# PowerSupply.net
KiCad netlist of a schematic drawn in Altium Designer
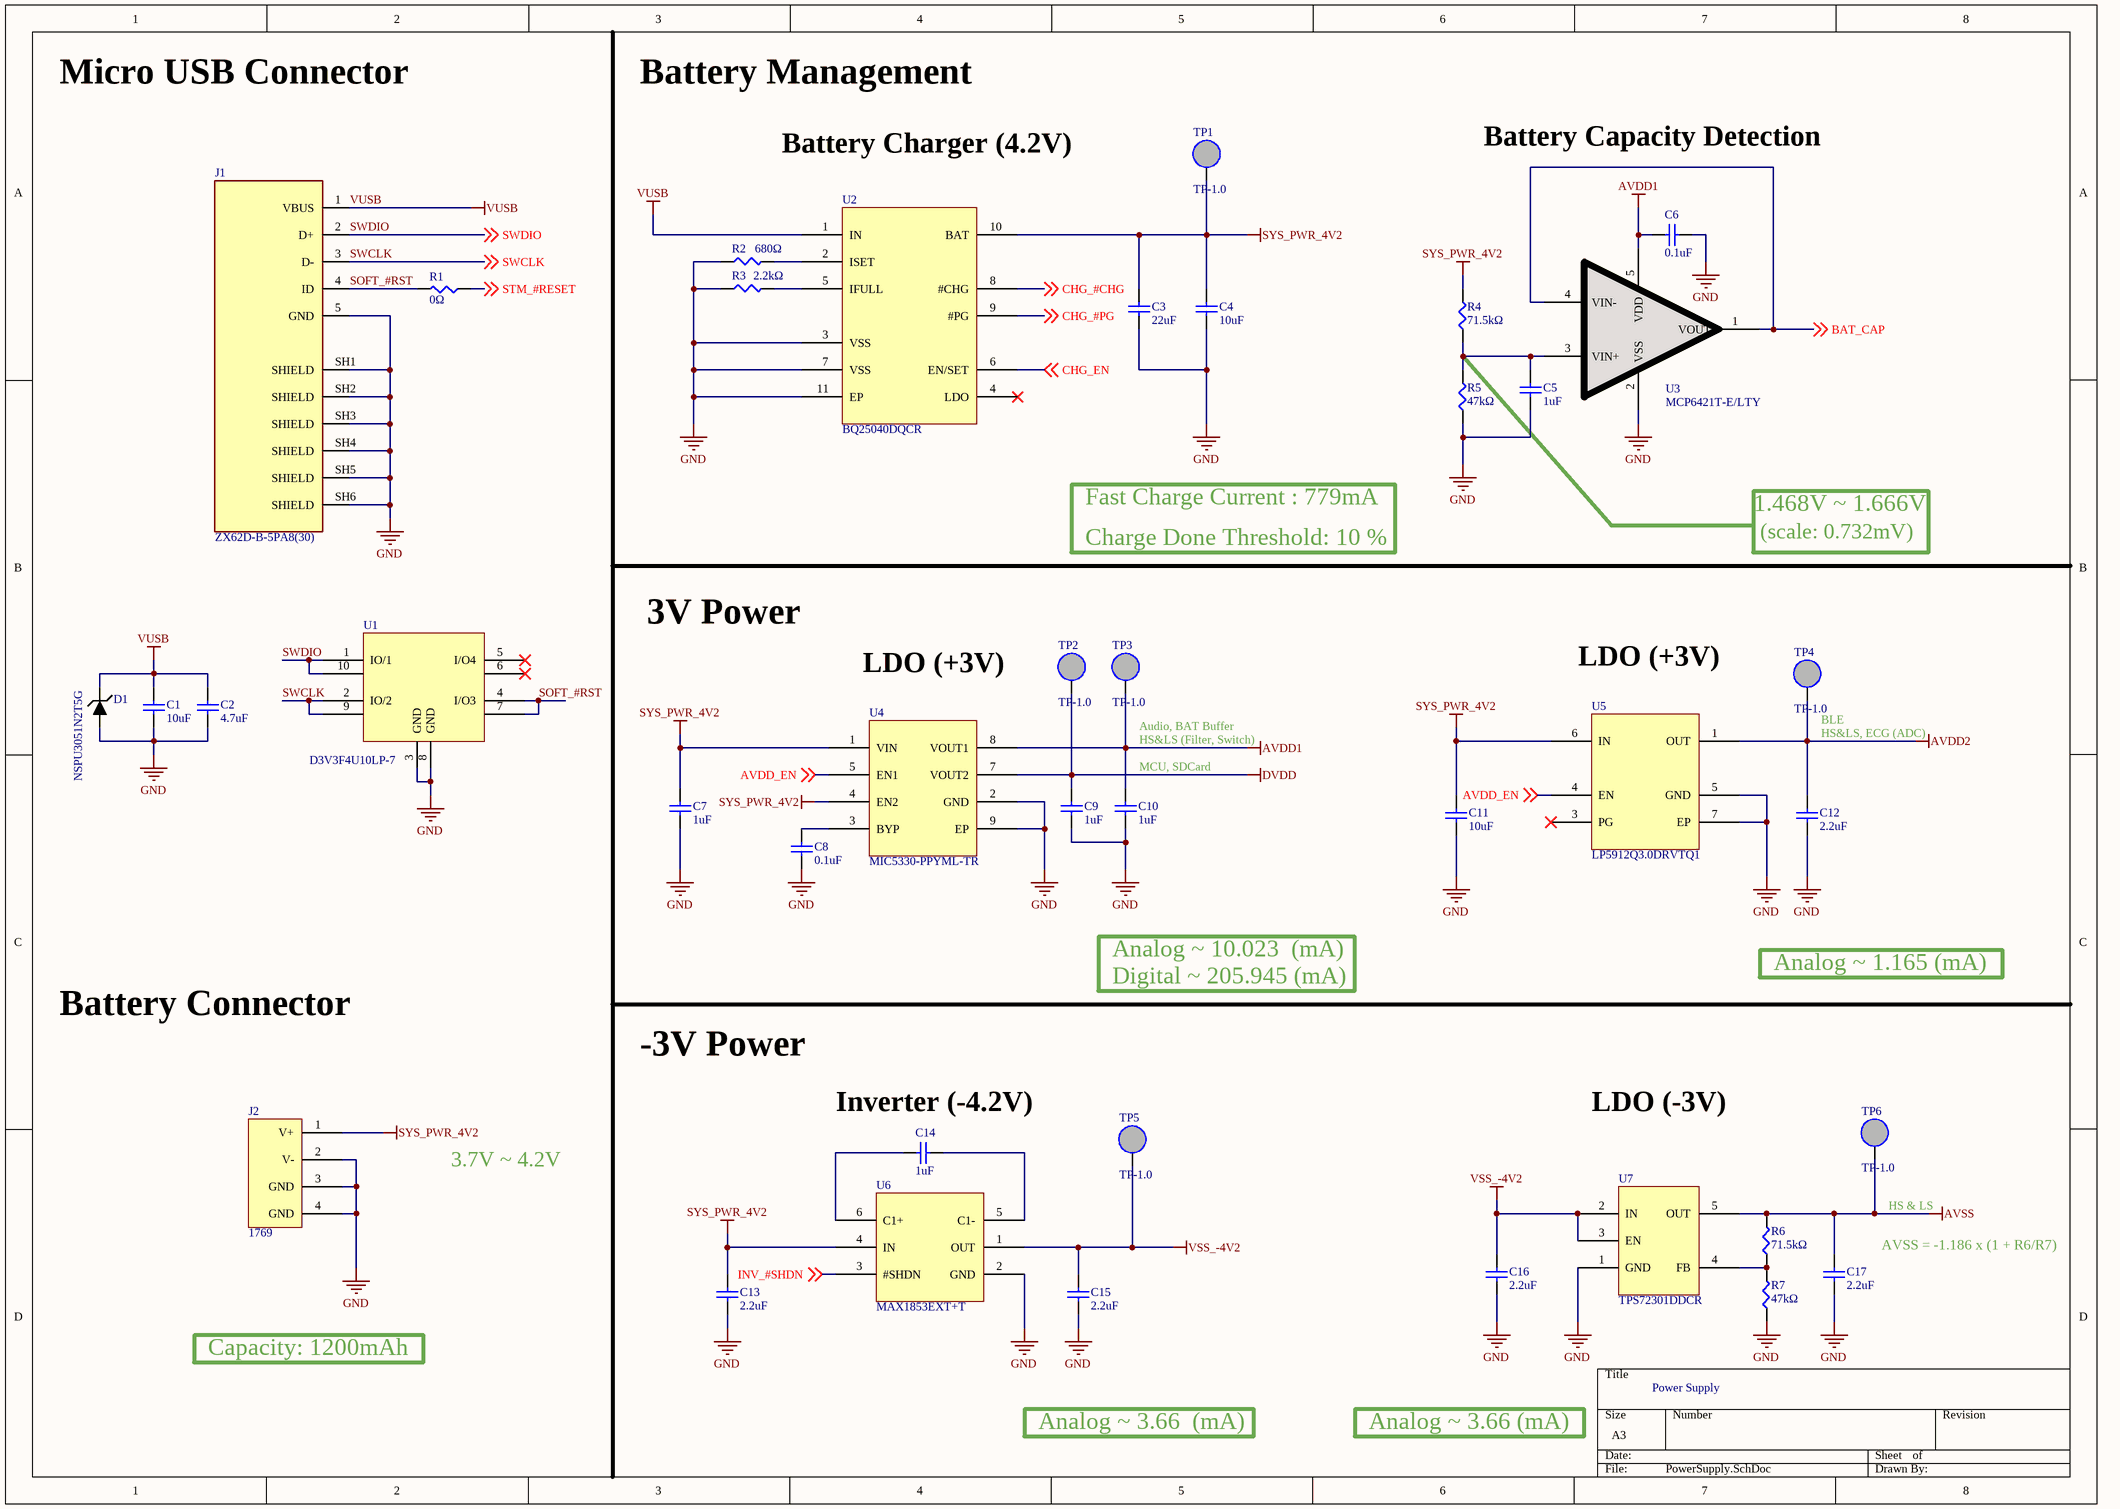
[diagram p0: PowerSupply.SchDoc]

(export (version "E")
  (design (tool "Eeschema 10.0.6"))
  (components
    (comp (ref "C1")
      (value "10uF")
      (footprint "0603")
      (description "MLCC-0603")
      (libsource (lib "MLCC") (part "0603"))
    )
    (comp (ref "C2")
      (value "4.7uF")
      (footprint "0603")
      (description "MLCC-0603")
      (libsource (lib "MLCC") (part "0603"))
    )
    (comp (ref "C3")
      (value "22uF")
      (footprint "0603")
      (description "MLCC-0603")
      (libsource (lib "MLCC") (part "0603"))
    )
    (comp (ref "C4")
      (value "10uF")
      (footprint "0603")
      (description "MLCC-0603")
      (libsource (lib "MLCC") (part "0603"))
    )
    (comp (ref "C5")
      (value "1uF")
      (footprint "0402")
      (description "MLCC-0402")
      (libsource (lib "MLCC") (part "0402"))
    )
    (comp (ref "C6")
      (value "0.1uF")
      (footprint "0402")
      (description "MLCC-0402")
      (libsource (lib "MLCC") (part "0402"))
    )
    (comp (ref "C7")
      (value "1uF")
      (footprint "0402")
      (description "MLCC-0402")
      (libsource (lib "MLCC") (part "0402"))
    )
    (comp (ref "C8")
      (value "0.1uF")
      (footprint "0402")
      (description "MLCC-0402")
      (libsource (lib "MLCC") (part "0402"))
    )
    (comp (ref "C9")
      (value "1uF")
      (footprint "0402")
      (description "MLCC-0402")
      (libsource (lib "MLCC") (part "0402"))
    )
    (comp (ref "C10")
      (value "1uF")
      (footprint "0402")
      (description "MLCC-0402")
      (libsource (lib "MLCC") (part "0402"))
    )
    (comp (ref "C11")
      (value "10uF")
      (footprint "0603")
      (description "MLCC-0603")
      (libsource (lib "MLCC") (part "0603"))
    )
    (comp (ref "C12")
      (value "2.2uF")
      (footprint "0402")
      (description "MLCC-0402")
      (libsource (lib "MLCC") (part "0402"))
    )
    (comp (ref "C13")
      (value "2.2uF")
      (footprint "0402")
      (description "MLCC-0402")
      (libsource (lib "MLCC") (part "0402"))
    )
    (comp (ref "C14")
      (value "1uF")
      (footprint "0402")
      (description "MLCC-0402")
      (libsource (lib "MLCC") (part "0402"))
    )
    (comp (ref "C15")
      (value "2.2uF")
      (footprint "0402")
      (description "MLCC-0402")
      (libsource (lib "MLCC") (part "0402"))
    )
    (comp (ref "C16")
      (value "2.2uF")
      (footprint "0402")
      (description "MLCC-0402")
      (libsource (lib "MLCC") (part "0402"))
    )
    (comp (ref "C17")
      (value "2.2uF")
      (footprint "0402")
      (description "MLCC-0402")
      (libsource (lib "MLCC") (part "0402"))
    )
    (comp (ref "D1")
      (value "NSPU3051N2T5G")
      (footprint "X2DFN-2(0.73-0.6x1.0x0.37)")
      (description "0016-11-ESD-01-D3V3F4U10LP-7")
      (fields (field (name "AUTHORBY") "yjlab"))
      (libsource (lib "NSPU3051") (part "NSPU3051N2T5G"))
    )
    (comp (ref "J1")
      (value "ZX62D-B-5PA8(30)")
      (footprint "HIROSE_ZX62D-B-5PA8(30)")
      (description "USB Connectors 5P RECEPTACLE")
      (libsource (lib "ZX62D-B-5PA8(30)") (part "ZX62D-B-5PA8(30)"))
    )
    (comp (ref "J2")
      (value "1769")
      (footprint "JST-PH 2-Pin")
      (description "Battery Connector, JST-PH 2 Pin")
      (libsource (lib "1769") (part "1769"))
    )
    (comp (ref "R1")
      (value "0Ω")
      (footprint "0402")
      (description "Resistor_SMD_0402")
      (fields (field (name "AUTHORBY") "yjlab"))
      (libsource (lib "Resistor") (part "0402"))
    )
    (comp (ref "R2")
      (value "680Ω")
      (footprint "0402")
      (description "Resistor_SMD_0402")
      (fields (field (name "AUTHORBY") "yjlab"))
      (libsource (lib "Resistor") (part "0402"))
    )
    (comp (ref "R3")
      (value "2.2kΩ")
      (footprint "0402")
      (description "Resistor_SMD_0402")
      (fields (field (name "AUTHORBY") "yjlab"))
      (libsource (lib "Resistor") (part "0402"))
    )
    (comp (ref "R4")
      (value "71.5kΩ")
      (footprint "0402")
      (description "Resistor_SMD_0402")
      (fields (field (name "AUTHORBY") "yjlab"))
      (libsource (lib "Resistor") (part "0402"))
    )
    (comp (ref "R5")
      (value "47kΩ")
      (footprint "0402")
      (description "Resistor_SMD_0402")
      (fields (field (name "AUTHORBY") "yjlab"))
      (libsource (lib "Resistor") (part "0402"))
    )
    (comp (ref "R6")
      (value "71.5kΩ")
      (footprint "0402")
      (description "Resistor_SMD_0402")
      (fields (field (name "AUTHORBY") "yjlab"))
      (libsource (lib "Resistor") (part "0402"))
    )
    (comp (ref "R7")
      (value "47kΩ")
      (footprint "0402")
      (description "Resistor_SMD_0402")
      (fields (field (name "AUTHORBY") "yjlab"))
      (libsource (lib "Resistor") (part "0402"))
    )
    (comp (ref "TP1")
      (value "TP-1.0")
      (footprint "Testpoint")
      (libsource (lib "Testpoint") (part "Testpoint"))
    )
    (comp (ref "TP2")
      (value "TP-1.0")
      (footprint "Testpoint")
      (libsource (lib "Testpoint") (part "Testpoint"))
    )
    (comp (ref "TP3")
      (value "TP-1.0")
      (footprint "Testpoint")
      (libsource (lib "Testpoint") (part "Testpoint"))
    )
    (comp (ref "TP4")
      (value "TP-1.0")
      (footprint "Testpoint")
      (libsource (lib "Testpoint") (part "Testpoint"))
    )
    (comp (ref "TP5")
      (value "TP-1.0")
      (footprint "Testpoint")
      (libsource (lib "Testpoint") (part "Testpoint"))
    )
    (comp (ref "TP6")
      (value "TP-1.0")
      (footprint "Testpoint")
      (libsource (lib "Testpoint") (part "Testpoint"))
    )
    (comp (ref "U1")
      (value "D3V3F4U10LP-7")
      (footprint "UDFN2510-10(0.5-1.0x2.5x0.575)")
      (description "0017-11-ESD-01-D3V3F4U10LP-7")
      (fields (field (name "AUTHORBY") "yjlab"))
      (libsource (lib "D3V3F4U10LP-7") (part "D3V3F4U10LP-7"))
    )
    (comp (ref "U2")
      (value "BQ25040DQCR")
      (footprint "WSON-10(0.5-2.0x3.0x0.8)")
      (description "0001-07-BAC-01-BQ25040DQCR")
      (fields (field (name "AUTHORBY") "yjlab"))
      (libsource (lib "BQ25040") (part "BQ25040DQCR"))
    )
    (comp (ref "U3")
      (value "MCP6421T-E/LTY")
      (footprint "SC-70-5")
      (description "4.4 µA/Amplifier, 90 kHz Op Amp")
      (libsource (lib "MCP642x") (part "MCP6421T-E/LTY"))
    )
    (comp (ref "U4")
      (value "MIC5330-PPYML-TR")
      (footprint "VFDFN-8")
      (description "Voltage Regulators Dual 300mA LDO, 2 Output: (3V, 3V)")
      (libsource (lib "MIC5330") (part "MIC5330-PPYML-TR"))
    )
    (comp (ref "U5")
      (value "LP5912Q3.0DRVTQ1")
      (footprint "WSON-6")
      (libsource (lib "LP5912-Q1") (part "LP5912Q3.0DRVTQ1"))
    )
    (comp (ref "U6")
      (value "MAX1853EXT+T")
      (footprint "SC70-6")
      (description "Switching Voltage Regulators SC70 Inverting Charge Pumps with Shutdown, Switching Frequency 200kHz")
      (libsource (lib "MAX1853") (part "MAX1853EXT+T"))
    )
    (comp (ref "U7")
      (value "TPS72301DDCR")
      (footprint "SOT-23-5")
      (description "Negative Output LDO, Adjustable Output")
      (libsource (lib "TPS723") (part "TPS72301DDCR"))
    )
  )
  (nets
    (net (code "1") (name "/SOFT_#RST") (class "Default")
      (node (ref "J1") (pin "4") (pinfunction "ID_4") (pintype "passive"))
      (node (ref "R1") (pin "2") (pinfunction "2_2") (pintype "passive"))
      (node (ref "U1") (pin "4") (pinfunction "I/O3_4") (pintype "passive"))
      (node (ref "U1") (pin "7") (pintype "passive"))
    )
    (net (code "2") (name "AVDD1") (class "Default")
      (node (ref "C10") (pin "2") (pinfunction "2_2") (pintype "passive"))
      (node (ref "C6") (pin "2") (pinfunction "2_2") (pintype "passive"))
      (node (ref "TP3") (pin "1") (pinfunction "1_1") (pintype "passive"))
      (node (ref "U3") (pin "5") (pinfunction "VDD_5") (pintype "passive"))
      (node (ref "U4") (pin "8") (pinfunction "VOUT1_8") (pintype "passive"))
    )
    (net (code "3") (name "AVDD2") (class "Default")
      (node (ref "C12") (pin "2") (pinfunction "2_2") (pintype "passive"))
      (node (ref "TP4") (pin "1") (pinfunction "1_1") (pintype "passive"))
      (node (ref "U5") (pin "1") (pinfunction "OUT_1") (pintype "passive"))
    )
    (net (code "4") (name "AVDD_EN") (class "Default")
      (node (ref "U4") (pin "5") (pinfunction "EN1_5") (pintype "passive"))
      (node (ref "U5") (pin "4") (pinfunction "EN_4") (pintype "passive"))
    )
    (net (code "5") (name "AVSS") (class "Default")
      (node (ref "C17") (pin "2") (pinfunction "2_2") (pintype "passive"))
      (node (ref "R6") (pin "2") (pinfunction "2_2") (pintype "passive"))
      (node (ref "TP6") (pin "1") (pinfunction "1_1") (pintype "passive"))
      (node (ref "U7") (pin "5") (pinfunction "OUT_5") (pintype "passive"))
    )
    (net (code "6") (name "BAT_CAP") (class "Default")
      (node (ref "U3") (pin "1") (pinfunction "VOUT_1") (pintype "passive"))
      (node (ref "U3") (pin "4") (pinfunction "VIN-_4") (pintype "passive"))
    )
    (net (code "7") (name "CHG_#CHG") (class "Default")
      (node (ref "U2") (pin "8") (pinfunction "#CHG_8") (pintype "passive"))
    )
    (net (code "8") (name "CHG_#PG") (class "Default")
      (node (ref "U2") (pin "9") (pinfunction "#PG_9") (pintype "passive"))
    )
    (net (code "9") (name "CHG_EN") (class "Default")
      (node (ref "U2") (pin "6") (pinfunction "EN/SET_6") (pintype "passive"))
    )
    (net (code "10") (name "DVDD") (class "Default")
      (node (ref "C9") (pin "2") (pinfunction "2_2") (pintype "passive"))
      (node (ref "TP2") (pin "1") (pinfunction "1_1") (pintype "passive"))
      (node (ref "U4") (pin "7") (pinfunction "VOUT2_7") (pintype "passive"))
    )
    (net (code "11") (name "GND") (class "Default")
      (node (ref "C1") (pin "1") (pinfunction "1_1") (pintype "passive"))
      (node (ref "C10") (pin "1") (pinfunction "1_1") (pintype "passive"))
      (node (ref "C11") (pin "1") (pinfunction "1_1") (pintype "passive"))
      (node (ref "C12") (pin "1") (pinfunction "1_1") (pintype "passive"))
      (node (ref "C13") (pin "1") (pinfunction "1_1") (pintype "passive"))
      (node (ref "C15") (pin "1") (pinfunction "1_1") (pintype "passive"))
      (node (ref "C16") (pin "1") (pinfunction "1_1") (pintype "passive"))
      (node (ref "C17") (pin "1") (pinfunction "1_1") (pintype "passive"))
      (node (ref "C2") (pin "1") (pinfunction "1_1") (pintype "passive"))
      (node (ref "C3") (pin "1") (pinfunction "1_1") (pintype "passive"))
      (node (ref "C4") (pin "1") (pinfunction "1_1") (pintype "passive"))
      (node (ref "C5") (pin "1") (pinfunction "1_1") (pintype "passive"))
      (node (ref "C6") (pin "1") (pinfunction "1_1") (pintype "passive"))
      (node (ref "C7") (pin "1") (pinfunction "1_1") (pintype "passive"))
      (node (ref "C8") (pin "1") (pinfunction "1_1") (pintype "passive"))
      (node (ref "C9") (pin "1") (pinfunction "1_1") (pintype "passive"))
      (node (ref "D1") (pin "2") (pinfunction "ANODE_2") (pintype "passive"))
      (node (ref "J1") (pin "5") (pinfunction "GND_5") (pintype "passive"))
      (node (ref "J1") (pin "SH1") (pinfunction "SHIELD_SH1") (pintype "power_in"))
      (node (ref "J1") (pin "SH2") (pinfunction "SHIELD_SH2") (pintype "power_in"))
      (node (ref "J1") (pin "SH3") (pinfunction "SHIELD_SH3") (pintype "power_in"))
      (node (ref "J1") (pin "SH4") (pinfunction "SHIELD_SH4") (pintype "power_in"))
      (node (ref "J1") (pin "SH5") (pinfunction "SHIELD_SH5") (pintype "power_in"))
      (node (ref "J1") (pin "SH6") (pinfunction "SHIELD_SH6") (pintype "power_in"))
      (node (ref "J2") (pin "2") (pinfunction "V-_2") (pintype "passive"))
      (node (ref "J2") (pin "3") (pinfunction "GND_3") (pintype "passive"))
      (node (ref "J2") (pin "4") (pinfunction "GND_4") (pintype "passive"))
      (node (ref "R2") (pin "1") (pinfunction "1_1") (pintype "passive"))
      (node (ref "R3") (pin "1") (pinfunction "1_1") (pintype "passive"))
      (node (ref "R5") (pin "1") (pinfunction "1_1") (pintype "passive"))
      (node (ref "R7") (pin "1") (pinfunction "1_1") (pintype "passive"))
      (node (ref "U1") (pin "3") (pinfunction "GND_3") (pintype "passive"))
      (node (ref "U1") (pin "8") (pinfunction "GND_8") (pintype "passive"))
      (node (ref "U2") (pin "11") (pinfunction "EP_11") (pintype "passive"))
      (node (ref "U2") (pin "3") (pinfunction "VSS_3") (pintype "passive"))
      (node (ref "U2") (pin "7") (pinfunction "VSS_7") (pintype "passive"))
      (node (ref "U3") (pin "2") (pinfunction "VSS_2") (pintype "passive"))
      (node (ref "U4") (pin "2") (pinfunction "GND_2") (pintype "passive"))
      (node (ref "U4") (pin "9") (pinfunction "EP_9") (pintype "passive"))
      (node (ref "U5") (pin "5") (pinfunction "GND_5") (pintype "passive"))
      (node (ref "U5") (pin "7") (pinfunction "EP_7") (pintype "passive"))
      (node (ref "U6") (pin "2") (pinfunction "GND_2") (pintype "passive"))
      (node (ref "U7") (pin "1") (pinfunction "GND_1") (pintype "passive"))
    )
    (net (code "12") (name "INV_#SHDN") (class "Default")
      (node (ref "U6") (pin "3") (pinfunction "#SHDN_3") (pintype "passive"))
    )
    (net (code "13") (name "Net-(U2-IFULL)") (class "Default")
      (node (ref "R3") (pin "2") (pinfunction "2_2") (pintype "passive"))
      (node (ref "U2") (pin "5") (pinfunction "IFULL_5") (pintype "passive"))
    )
    (net (code "14") (name "Net-(U2-ISET)") (class "Default")
      (node (ref "R2") (pin "2") (pinfunction "2_2") (pintype "passive"))
      (node (ref "U2") (pin "2") (pinfunction "ISET_2") (pintype "passive"))
    )
    (net (code "15") (name "Net-(U3-VIN+)") (class "Default")
      (node (ref "C5") (pin "2") (pinfunction "2_2") (pintype "passive"))
      (node (ref "R4") (pin "1") (pinfunction "1_1") (pintype "passive"))
      (node (ref "R5") (pin "2") (pinfunction "2_2") (pintype "passive"))
      (node (ref "U3") (pin "3") (pinfunction "VIN+_3") (pintype "passive"))
    )
    (net (code "16") (name "Net-(U4-BYP)") (class "Default")
      (node (ref "C8") (pin "2") (pinfunction "2_2") (pintype "passive"))
      (node (ref "U4") (pin "3") (pinfunction "BYP_3") (pintype "passive"))
    )
    (net (code "17") (name "Net-(U6-C1+)") (class "Default")
      (node (ref "C14") (pin "1") (pinfunction "1_1") (pintype "passive"))
      (node (ref "U6") (pin "6") (pinfunction "C1+_6") (pintype "passive"))
    )
    (net (code "18") (name "Net-(U6-C1-)") (class "Default")
      (node (ref "C14") (pin "2") (pinfunction "2_2") (pintype "passive"))
      (node (ref "U6") (pin "5") (pinfunction "C1-_5") (pintype "passive"))
    )
    (net (code "19") (name "Net-(U7-FB)") (class "Default")
      (node (ref "R6") (pin "1") (pinfunction "1_1") (pintype "passive"))
      (node (ref "R7") (pin "2") (pinfunction "2_2") (pintype "passive"))
      (node (ref "U7") (pin "4") (pinfunction "FB_4") (pintype "passive"))
    )
    (net (code "20") (name "STM_#RESET") (class "Default")
      (node (ref "R1") (pin "1") (pinfunction "1_1") (pintype "passive"))
    )
    (net (code "21") (name "SWCLK") (class "Default")
      (node (ref "J1") (pin "3") (pinfunction "D-_3") (pintype "passive"))
      (node (ref "U1") (pin "2") (pinfunction "IO/2_2") (pintype "passive"))
      (node (ref "U1") (pin "9") (pintype "passive"))
    )
    (net (code "22") (name "SWDIO") (class "Default")
      (node (ref "J1") (pin "2") (pinfunction "D+_2") (pintype "passive"))
      (node (ref "U1") (pin "1") (pinfunction "IO/1_1") (pintype "passive"))
      (node (ref "U1") (pin "10") (pintype "passive"))
    )
    (net (code "23") (name "SYS_PWR_4V2") (class "Default")
      (node (ref "C11") (pin "2") (pinfunction "2_2") (pintype "passive"))
      (node (ref "C13") (pin "2") (pinfunction "2_2") (pintype "passive"))
      (node (ref "C3") (pin "2") (pinfunction "2_2") (pintype "passive"))
      (node (ref "C4") (pin "2") (pinfunction "2_2") (pintype "passive"))
      (node (ref "C7") (pin "2") (pinfunction "2_2") (pintype "passive"))
      (node (ref "J2") (pin "1") (pinfunction "V+_1") (pintype "passive"))
      (node (ref "R4") (pin "2") (pinfunction "2_2") (pintype "passive"))
      (node (ref "TP1") (pin "1") (pinfunction "1_1") (pintype "passive"))
      (node (ref "U2") (pin "10") (pinfunction "BAT_10") (pintype "passive"))
      (node (ref "U4") (pin "1") (pinfunction "VIN_1") (pintype "passive"))
      (node (ref "U4") (pin "4") (pinfunction "EN2_4") (pintype "passive"))
      (node (ref "U5") (pin "6") (pinfunction "IN_6") (pintype "passive"))
      (node (ref "U6") (pin "4") (pinfunction "IN_4") (pintype "passive"))
    )
    (net (code "24") (name "VSS_-4V2") (class "Default")
      (node (ref "C15") (pin "2") (pinfunction "2_2") (pintype "passive"))
      (node (ref "C16") (pin "2") (pinfunction "2_2") (pintype "passive"))
      (node (ref "TP5") (pin "1") (pinfunction "1_1") (pintype "passive"))
      (node (ref "U6") (pin "1") (pinfunction "OUT_1") (pintype "passive"))
      (node (ref "U7") (pin "2") (pinfunction "IN_2") (pintype "passive"))
      (node (ref "U7") (pin "3") (pinfunction "EN_3") (pintype "passive"))
    )
    (net (code "25") (name "VUSB") (class "Default")
      (node (ref "C1") (pin "2") (pinfunction "2_2") (pintype "passive"))
      (node (ref "C2") (pin "2") (pinfunction "2_2") (pintype "passive"))
      (node (ref "D1") (pin "1") (pinfunction "CATHODE_1") (pintype "passive"))
      (node (ref "J1") (pin "1") (pinfunction "VBUS_1") (pintype "passive"))
      (node (ref "U2") (pin "1") (pinfunction "IN_1") (pintype "passive"))
    )
    (net (code "26") (name "unconnected-(U1-I{slash}O4-Pad5)") (class "Default")
      (node (ref "U1") (pin "5") (pinfunction "I/O4_5") (pintype "passive+no_connect"))
    )
    (net (code "27") (name "unconnected-(U1-Pad6)") (class "Default")
      (node (ref "U1") (pin "6") (pintype "passive+no_connect"))
    )
    (net (code "28") (name "unconnected-(U2-LDO-Pad4)") (class "Default")
      (node (ref "U2") (pin "4") (pinfunction "LDO_4") (pintype "passive+no_connect"))
    )
    (net (code "29") (name "unconnected-(U5-PG-Pad3)") (class "Default")
      (node (ref "U5") (pin "3") (pinfunction "PG_3") (pintype "passive+no_connect"))
    )
  )
)
